# chicken_hw.net
KiCad netlist of a schematic drawn in EAGLE
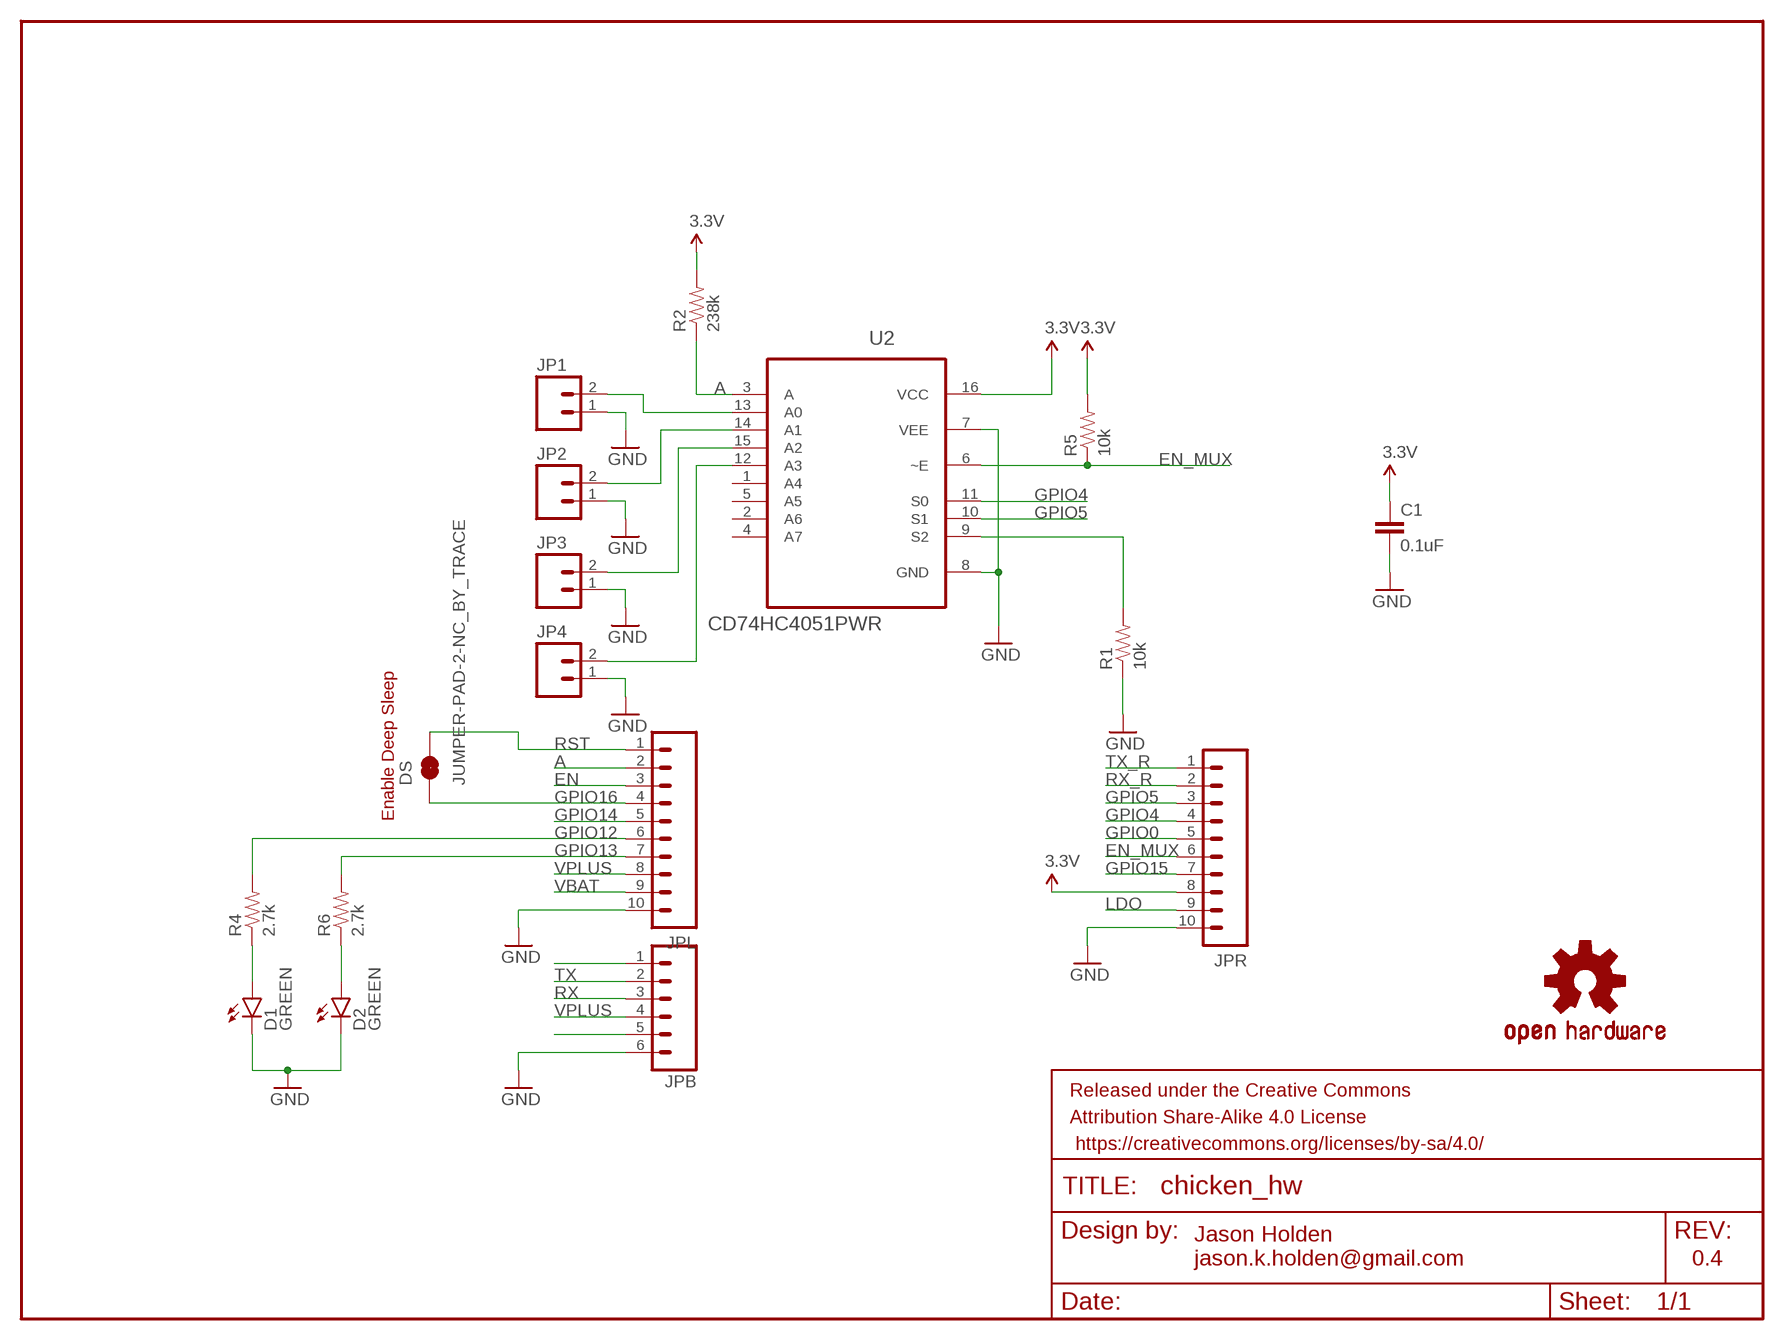
[diagram p0: schematic, sheet 1]

(export (version "E")
  (design (tool "Eeschema 10.0.6"))
  (components
    (comp (ref "C1")
      (value "0.1uF")
      (footprint "eagle-import:0603-CAP")
      (libsource (lib "eagle-import") (part "CAP0603-CAP"))
    )
    (comp (ref "D1")
      (value "GREEN")
      (footprint "eagle-import:LED-0603")
      (libsource (lib "eagle-import") (part "LED-GREEN0603"))
    )
    (comp (ref "D2")
      (value "GREEN")
      (footprint "eagle-import:LED-0603")
      (libsource (lib "eagle-import") (part "LED-GREEN0603"))
    )
    (comp (ref "DS")
      (value "JUMPER-PAD-2-NC_BY_TRACE")
      (footprint "eagle-import:PAD-JUMPER-2-NC_BY_TRACE_YES_SILK")
      (libsource (lib "eagle-import") (part "JUMPER-PAD-2-NC_BY_TRACE"))
    )
    (comp (ref "FRAME1")
      (value "FRAME-LETTER")
      (footprint "eagle-import:CREATIVE_COMMONS")
      (libsource (lib "eagle-import") (part "FRAME-LETTER"))
    )
    (comp (ref "JP1")
      (value "M02PTH")
      (footprint "eagle-import:1X02")
      (libsource (lib "eagle-import") (part "M02PTH"))
    )
    (comp (ref "JP2")
      (value "M02PTH")
      (footprint "eagle-import:1X02")
      (libsource (lib "eagle-import") (part "M02PTH"))
    )
    (comp (ref "JP3")
      (value "M02PTH")
      (footprint "eagle-import:1X02")
      (libsource (lib "eagle-import") (part "M02PTH"))
    )
    (comp (ref "JP4")
      (value "M02PTH")
      (footprint "eagle-import:1X02")
      (libsource (lib "eagle-import") (part "M02PTH"))
    )
    (comp (ref "JPB")
      (value "M06SILK_FEMALE_PTH")
      (footprint "eagle-import:1X06")
      (libsource (lib "eagle-import") (part "M06SILK_FEMALE_PTH"))
    )
    (comp (ref "JPL")
      (value "M10SILK_FEMALE_PTH")
      (footprint "eagle-import:1X10")
      (libsource (lib "eagle-import") (part "M10SILK_FEMALE_PTH"))
    )
    (comp (ref "JPR")
      (value "M10SILK_FEMALE_PTH")
      (footprint "eagle-import:1X10")
      (libsource (lib "eagle-import") (part "M10SILK_FEMALE_PTH"))
    )
    (comp (ref "LOGO1")
      (value "OSHW-LOGOS")
      (footprint "eagle-import:OSHW-LOGO-S")
      (libsource (lib "eagle-import") (part "OSHW-LOGOS"))
    )
    (comp (ref "R1")
      (value "10k")
      (footprint "eagle-import:0603-RES")
      (libsource (lib "eagle-import") (part "RESISTOR0603"))
    )
    (comp (ref "R2")
      (value "238k")
      (footprint "eagle-import:0603-RES")
      (libsource (lib "eagle-import") (part "RESISTOR0603"))
    )
    (comp (ref "R4")
      (value "2.7k")
      (footprint "eagle-import:0603-RES")
      (libsource (lib "eagle-import") (part "RESISTOR0603"))
    )
    (comp (ref "R5")
      (value "10k")
      (footprint "eagle-import:0603-RES")
      (libsource (lib "eagle-import") (part "RESISTOR0603"))
    )
    (comp (ref "R6")
      (value "2.7k")
      (footprint "eagle-import:0603-RES")
      (libsource (lib "eagle-import") (part "RESISTOR0603"))
    )
    (comp (ref "U2")
      (value "CD74HC4051PWR")
      (footprint "eagle-import:SOP65P640X120-16N")
      (libsource (lib "eagle-import") (part "CD74HC4051PWR"))
    )
  )
  (nets
    (net (code "1") (name "/A") (class "Default")
      (node (ref "JPL") (pin "2") (pinfunction "2_2") (pintype "passive"))
      (node (ref "R2") (pin "1") (pinfunction "1_1") (pintype "passive"))
      (node (ref "U2") (pin "3") (pinfunction "A_3") (pintype "bidirectional"))
    )
    (net (code "2") (name "/EN") (class "Default")
      (node (ref "JPL") (pin "3") (pinfunction "3_3") (pintype "passive"))
    )
    (net (code "3") (name "/EN_MUX") (class "Default")
      (node (ref "JPR") (pin "6") (pinfunction "6_6") (pintype "passive"))
      (node (ref "R5") (pin "1") (pinfunction "1_1") (pintype "passive"))
      (node (ref "U2") (pin "6") (pinfunction "~{E}_6") (pintype "input"))
    )
    (net (code "4") (name "/GPIO0") (class "Default")
      (node (ref "JPR") (pin "5") (pinfunction "5_5") (pintype "passive"))
    )
    (net (code "5") (name "/GPIO4") (class "Default")
      (node (ref "JPR") (pin "4") (pinfunction "4_4") (pintype "passive"))
      (node (ref "U2") (pin "11") (pinfunction "S0_11") (pintype "input"))
    )
    (net (code "6") (name "/GPIO5") (class "Default")
      (node (ref "JPR") (pin "3") (pinfunction "3_3") (pintype "passive"))
      (node (ref "U2") (pin "10") (pinfunction "S1_10") (pintype "input"))
    )
    (net (code "7") (name "/GPIO12") (class "Default")
      (node (ref "JPL") (pin "6") (pinfunction "6_6") (pintype "passive"))
      (node (ref "R4") (pin "2") (pinfunction "2_2") (pintype "passive"))
    )
    (net (code "8") (name "/GPIO13") (class "Default")
      (node (ref "JPL") (pin "7") (pinfunction "7_7") (pintype "passive"))
      (node (ref "R6") (pin "2") (pinfunction "2_2") (pintype "passive"))
    )
    (net (code "9") (name "/GPIO14") (class "Default")
      (node (ref "JPL") (pin "5") (pinfunction "5_5") (pintype "passive"))
    )
    (net (code "10") (name "/GPIO15") (class "Default")
      (node (ref "JPR") (pin "7") (pinfunction "7_7") (pintype "passive"))
    )
    (net (code "11") (name "/GPIO16") (class "Default")
      (node (ref "DS") (pin "1") (pinfunction "1_1") (pintype "passive"))
      (node (ref "JPL") (pin "4") (pinfunction "4_4") (pintype "passive"))
    )
    (net (code "12") (name "/LDO") (class "Default")
      (node (ref "JPR") (pin "9") (pinfunction "9_9") (pintype "passive"))
    )
    (net (code "13") (name "/RST") (class "Default")
      (node (ref "DS") (pin "2") (pinfunction "2_2") (pintype "passive"))
      (node (ref "JPL") (pin "1") (pinfunction "1_1") (pintype "passive"))
    )
    (net (code "14") (name "/RX") (class "Default")
      (node (ref "JPB") (pin "3") (pinfunction "3_3") (pintype "passive"))
    )
    (net (code "15") (name "/RX_R") (class "Default")
      (node (ref "JPR") (pin "2") (pinfunction "2_2") (pintype "passive"))
    )
    (net (code "16") (name "/TX") (class "Default")
      (node (ref "JPB") (pin "2") (pinfunction "2_2") (pintype "passive"))
    )
    (net (code "17") (name "/TX_R") (class "Default")
      (node (ref "JPR") (pin "1") (pinfunction "1_1") (pintype "passive"))
    )
    (net (code "18") (name "/VBAT") (class "Default")
      (node (ref "JPL") (pin "9") (pinfunction "9_9") (pintype "passive"))
    )
    (net (code "19") (name "/VPLUS") (class "Default")
      (node (ref "JPB") (pin "4") (pinfunction "4_4") (pintype "passive"))
      (node (ref "JPL") (pin "8") (pinfunction "8_8") (pintype "passive"))
    )
    (net (code "20") (name "3.3V") (class "Default")
      (node (ref "C1") (pin "1") (pinfunction "1_1") (pintype "passive"))
      (node (ref "JPR") (pin "8") (pinfunction "8_8") (pintype "passive"))
      (node (ref "R2") (pin "2") (pinfunction "2_2") (pintype "passive"))
      (node (ref "R5") (pin "2") (pinfunction "2_2") (pintype "passive"))
      (node (ref "U2") (pin "16") (pinfunction "VCC_16") (pintype "power_in"))
    )
    (net (code "21") (name "GND") (class "Default")
      (node (ref "C1") (pin "2") (pinfunction "2_2") (pintype "passive"))
      (node (ref "D1") (pin "C") (pinfunction "C_C") (pintype "passive"))
      (node (ref "D2") (pin "C") (pinfunction "C_C") (pintype "passive"))
      (node (ref "JP1") (pin "1") (pinfunction "1_1") (pintype "passive"))
      (node (ref "JP2") (pin "1") (pinfunction "1_1") (pintype "passive"))
      (node (ref "JP3") (pin "1") (pinfunction "1_1") (pintype "passive"))
      (node (ref "JP4") (pin "1") (pinfunction "1_1") (pintype "passive"))
      (node (ref "JPB") (pin "6") (pinfunction "6_6") (pintype "passive"))
      (node (ref "JPL") (pin "10") (pinfunction "10_10") (pintype "passive"))
      (node (ref "JPR") (pin "10") (pinfunction "10_10") (pintype "passive"))
      (node (ref "R1") (pin "1") (pinfunction "1_1") (pintype "passive"))
      (node (ref "U2") (pin "7") (pinfunction "VEE_7") (pintype "power_in"))
      (node (ref "U2") (pin "8") (pinfunction "GND_8") (pintype "passive"))
    )
    (net (code "22") (name "Net-(D1-PadA)") (class "Default")
      (node (ref "D1") (pin "A") (pinfunction "A_A") (pintype "passive"))
      (node (ref "R4") (pin "1") (pinfunction "1_1") (pintype "passive"))
    )
    (net (code "23") (name "Net-(D2-PadA)") (class "Default")
      (node (ref "D2") (pin "A") (pinfunction "A_A") (pintype "passive"))
      (node (ref "R6") (pin "1") (pinfunction "1_1") (pintype "passive"))
    )
    (net (code "24") (name "Net-(U2-A0)") (class "Default")
      (node (ref "JP1") (pin "2") (pinfunction "2_2") (pintype "passive"))
      (node (ref "U2") (pin "13") (pinfunction "A0_13") (pintype "bidirectional"))
    )
    (net (code "25") (name "Net-(U2-A1)") (class "Default")
      (node (ref "JP2") (pin "2") (pinfunction "2_2") (pintype "passive"))
      (node (ref "U2") (pin "14") (pinfunction "A1_14") (pintype "bidirectional"))
    )
    (net (code "26") (name "Net-(U2-A2)") (class "Default")
      (node (ref "JP3") (pin "2") (pinfunction "2_2") (pintype "passive"))
      (node (ref "U2") (pin "15") (pinfunction "A2_15") (pintype "bidirectional"))
    )
    (net (code "27") (name "Net-(U2-A3)") (class "Default")
      (node (ref "JP4") (pin "2") (pinfunction "2_2") (pintype "passive"))
      (node (ref "U2") (pin "12") (pinfunction "A3_12") (pintype "bidirectional"))
    )
    (net (code "28") (name "Net-(U2-S2)") (class "Default")
      (node (ref "R1") (pin "2") (pinfunction "2_2") (pintype "passive"))
      (node (ref "U2") (pin "9") (pinfunction "S2_9") (pintype "input"))
    )
    (net (code "29") (name "unconnected-(JPB-Pad1)") (class "Default")
      (node (ref "JPB") (pin "1") (pinfunction "1_1") (pintype "passive"))
    )
    (net (code "30") (name "unconnected-(JPB-Pad5)") (class "Default")
      (node (ref "JPB") (pin "5") (pinfunction "5_5") (pintype "passive"))
    )
    (net (code "31") (name "unconnected-(U2-A4-Pad1)") (class "Default")
      (node (ref "U2") (pin "1") (pinfunction "A4_1") (pintype "bidirectional"))
    )
    (net (code "32") (name "unconnected-(U2-A5-Pad5)") (class "Default")
      (node (ref "U2") (pin "5") (pinfunction "A5_5") (pintype "bidirectional"))
    )
    (net (code "33") (name "unconnected-(U2-A6-Pad2)") (class "Default")
      (node (ref "U2") (pin "2") (pinfunction "A6_2") (pintype "bidirectional"))
    )
    (net (code "34") (name "unconnected-(U2-A7-Pad4)") (class "Default")
      (node (ref "U2") (pin "4") (pinfunction "A7_4") (pintype "bidirectional"))
    )
  )
)
